# charlie_heart.net
KiCad netlist of a schematic drawn in EAGLE
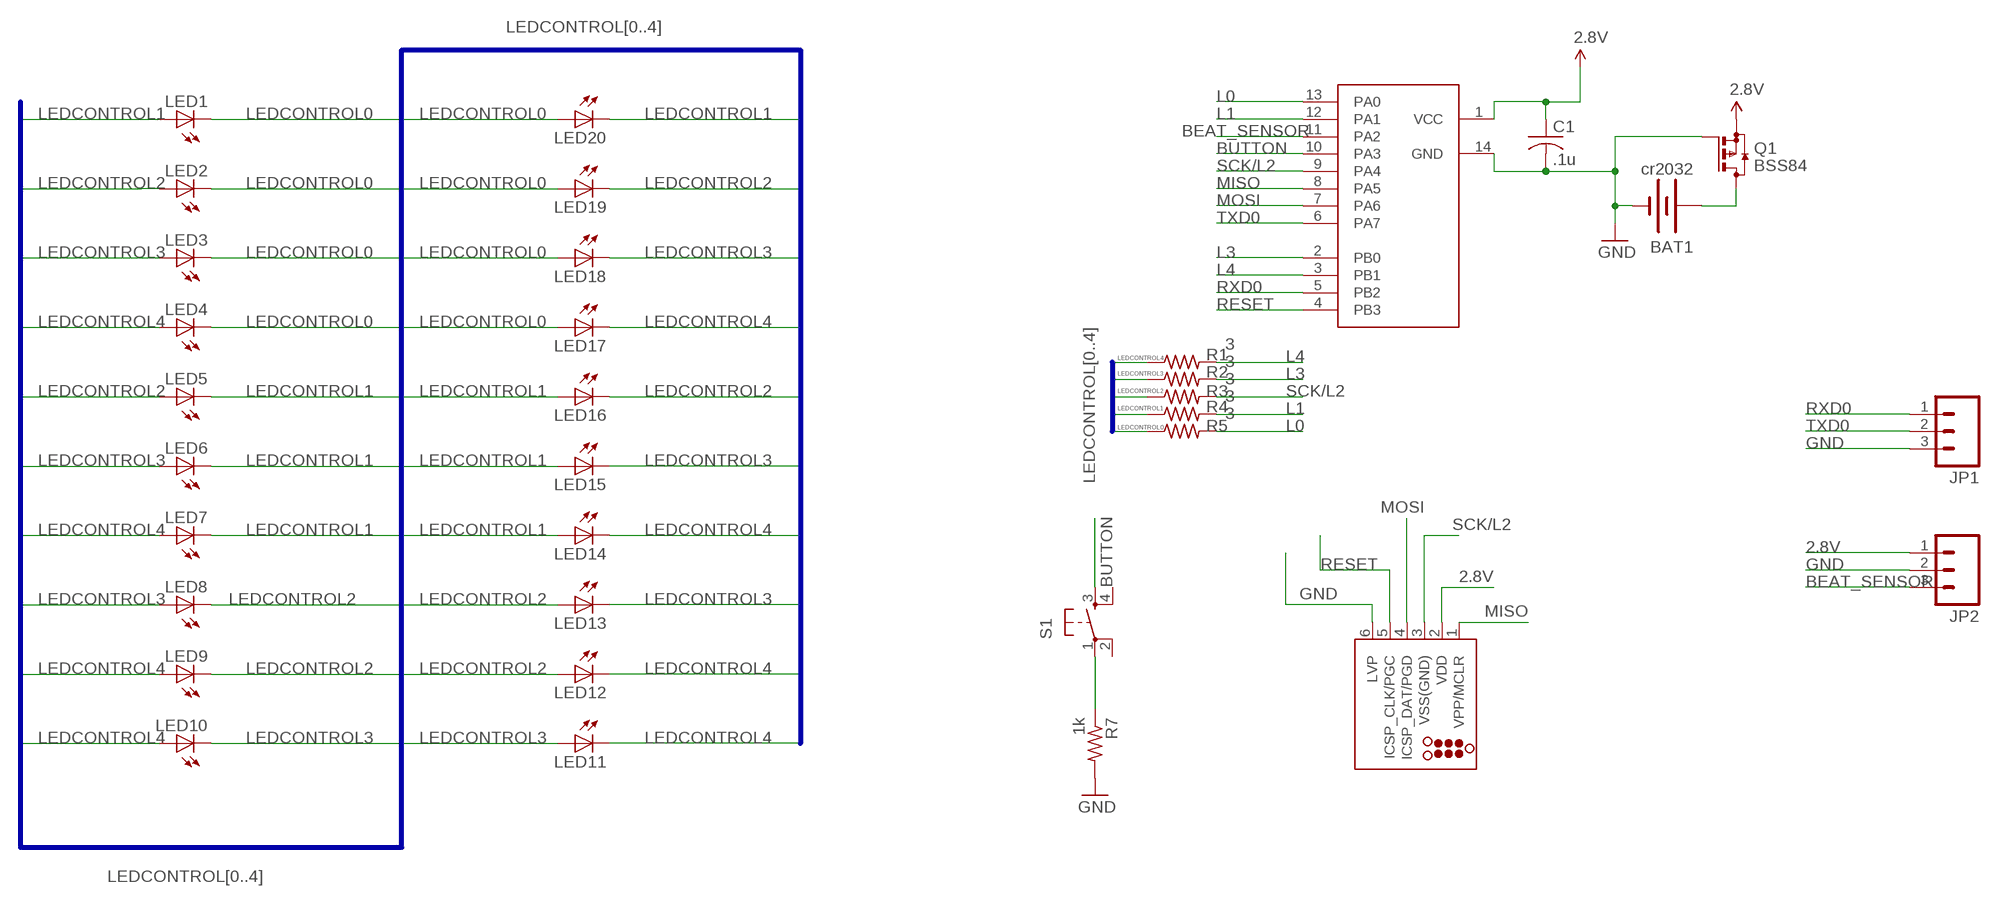
[diagram p0: schematic, sheet 1]

(export (version "E")
  (design (tool "Eeschema 10.0.6"))
  (components
    (comp (ref "BAT1")
      (value "cr2032")
      (footprint "eagle-import:BATTCON_20MM")
      (libsource (lib "eagle-import") (part "BATTERY20SMD"))
    )
    (comp (ref "C1")
      (value ".1u")
      (footprint "eagle-import:C1206")
      (libsource (lib "eagle-import") (part "C-USC1206"))
    )
    (comp (ref "J1")
      (value "TC2030-MCP-NL")
      (footprint "eagle-import:TC2030-MCP-NL")
      (libsource (lib "eagle-import") (part "TC2030-MCP-NL"))
    )
    (comp (ref "JP1")
      (value "M031X03_NO_SILK")
      (footprint "eagle-import:1X03_NO_SILK")
      (libsource (lib "eagle-import") (part "M031X03_NO_SILK"))
    )
    (comp (ref "JP2")
      (value "M031X03_NO_SILK")
      (footprint "eagle-import:1X03_NO_SILK")
      (libsource (lib "eagle-import") (part "M031X03_NO_SILK"))
    )
    (comp (ref "LED1")
      (value "LEDCHIP-LED0805")
      (footprint "eagle-import:CHIP-LED0805")
      (libsource (lib "eagle-import") (part "LEDCHIP-LED0805"))
    )
    (comp (ref "LED2")
      (value "LEDCHIP-LED0805")
      (footprint "eagle-import:CHIP-LED0805")
      (libsource (lib "eagle-import") (part "LEDCHIP-LED0805"))
    )
    (comp (ref "LED3")
      (value "LEDCHIP-LED0805")
      (footprint "eagle-import:CHIP-LED0805")
      (libsource (lib "eagle-import") (part "LEDCHIP-LED0805"))
    )
    (comp (ref "LED4")
      (value "LEDCHIP-LED0805")
      (footprint "eagle-import:CHIP-LED0805")
      (libsource (lib "eagle-import") (part "LEDCHIP-LED0805"))
    )
    (comp (ref "LED5")
      (value "LEDCHIP-LED0805")
      (footprint "eagle-import:CHIP-LED0805")
      (libsource (lib "eagle-import") (part "LEDCHIP-LED0805"))
    )
    (comp (ref "LED6")
      (value "LEDCHIP-LED0805")
      (footprint "eagle-import:CHIP-LED0805")
      (libsource (lib "eagle-import") (part "LEDCHIP-LED0805"))
    )
    (comp (ref "LED7")
      (value "LEDCHIP-LED0805")
      (footprint "eagle-import:CHIP-LED0805")
      (libsource (lib "eagle-import") (part "LEDCHIP-LED0805"))
    )
    (comp (ref "LED8")
      (value "LEDCHIP-LED0805")
      (footprint "eagle-import:CHIP-LED0805")
      (libsource (lib "eagle-import") (part "LEDCHIP-LED0805"))
    )
    (comp (ref "LED9")
      (value "LEDCHIP-LED0805")
      (footprint "eagle-import:CHIP-LED0805")
      (libsource (lib "eagle-import") (part "LEDCHIP-LED0805"))
    )
    (comp (ref "LED10")
      (value "LEDCHIP-LED0805")
      (footprint "eagle-import:CHIP-LED0805")
      (libsource (lib "eagle-import") (part "LEDCHIP-LED0805"))
    )
    (comp (ref "LED11")
      (value "LEDCHIP-LED0805")
      (footprint "eagle-import:CHIP-LED0805")
      (libsource (lib "eagle-import") (part "LEDCHIP-LED0805"))
    )
    (comp (ref "LED12")
      (value "LEDCHIP-LED0805")
      (footprint "eagle-import:CHIP-LED0805")
      (libsource (lib "eagle-import") (part "LEDCHIP-LED0805"))
    )
    (comp (ref "LED13")
      (value "LEDCHIP-LED0805")
      (footprint "eagle-import:CHIP-LED0805")
      (libsource (lib "eagle-import") (part "LEDCHIP-LED0805"))
    )
    (comp (ref "LED14")
      (value "LEDCHIP-LED0805")
      (footprint "eagle-import:CHIP-LED0805")
      (libsource (lib "eagle-import") (part "LEDCHIP-LED0805"))
    )
    (comp (ref "LED15")
      (value "LEDCHIP-LED0805")
      (footprint "eagle-import:CHIP-LED0805")
      (libsource (lib "eagle-import") (part "LEDCHIP-LED0805"))
    )
    (comp (ref "LED16")
      (value "LEDCHIP-LED0805")
      (footprint "eagle-import:CHIP-LED0805")
      (libsource (lib "eagle-import") (part "LEDCHIP-LED0805"))
    )
    (comp (ref "LED17")
      (value "LEDCHIP-LED0805")
      (footprint "eagle-import:CHIP-LED0805")
      (libsource (lib "eagle-import") (part "LEDCHIP-LED0805"))
    )
    (comp (ref "LED18")
      (value "LEDCHIP-LED0805")
      (footprint "eagle-import:CHIP-LED0805")
      (libsource (lib "eagle-import") (part "LEDCHIP-LED0805"))
    )
    (comp (ref "LED19")
      (value "LEDCHIP-LED0805")
      (footprint "eagle-import:CHIP-LED0805")
      (libsource (lib "eagle-import") (part "LEDCHIP-LED0805"))
    )
    (comp (ref "LED20")
      (value "LEDCHIP-LED0805")
      (footprint "eagle-import:CHIP-LED0805")
      (libsource (lib "eagle-import") (part "LEDCHIP-LED0805"))
    )
    (comp (ref "Q1")
      (value "BSS84")
      (footprint "eagle-import:SOT23")
      (libsource (lib "eagle-import") (part "BSS84"))
    )
    (comp (ref "R1")
      (value "3")
      (footprint "eagle-import:R0805")
      (libsource (lib "eagle-import") (part "R-US_R0805"))
    )
    (comp (ref "R2")
      (value "3")
      (footprint "eagle-import:R0805")
      (libsource (lib "eagle-import") (part "R-US_R0805"))
    )
    (comp (ref "R3")
      (value "3")
      (footprint "eagle-import:R0805")
      (libsource (lib "eagle-import") (part "R-US_R0805"))
    )
    (comp (ref "R4")
      (value "3")
      (footprint "eagle-import:R0805")
      (libsource (lib "eagle-import") (part "R-US_R0805"))
    )
    (comp (ref "R5")
      (value "3")
      (footprint "eagle-import:R0805")
      (libsource (lib "eagle-import") (part "R-US_R0805"))
    )
    (comp (ref "R7")
      (value "1k")
      (footprint "eagle-import:R0805")
      (libsource (lib "eagle-import") (part "R-US_R0805"))
    )
    (comp (ref "S1")
      (value "TAC_SWITCHSMD")
      (footprint "eagle-import:TACTILE_SWITCH_SMD")
      (libsource (lib "eagle-import") (part "TAC_SWITCHSMD"))
    )
    (comp (ref "U1")
      (value "ATTINY841")
      (footprint "eagle-import:SOIC127P600X175-14N")
      (libsource (lib "eagle-import") (part "ATTINY841-SSU"))
    )
  )
  (nets
    (net (code "1") (name "/BEAT_SENSOR") (class "Default")
      (node (ref "JP2") (pin "3") (pinfunction "3_3") (pintype "passive"))
      (node (ref "U1") (pin "11") (pinfunction "PA2_11") (pintype "bidirectional"))
    )
    (net (code "2") (name "/BUTTON") (class "Default")
      (node (ref "S1") (pin "3") (pinfunction "3_3") (pintype "passive"))
      (node (ref "U1") (pin "10") (pinfunction "PA3_10") (pintype "bidirectional"))
    )
    (net (code "3") (name "/L0") (class "Default")
      (node (ref "R5") (pin "2") (pinfunction "2_2") (pintype "passive"))
      (node (ref "U1") (pin "13") (pinfunction "PA0_13") (pintype "bidirectional"))
    )
    (net (code "4") (name "/L1") (class "Default")
      (node (ref "R4") (pin "2") (pinfunction "2_2") (pintype "passive"))
      (node (ref "U1") (pin "12") (pinfunction "PA1_12") (pintype "bidirectional"))
    )
    (net (code "5") (name "/L3") (class "Default")
      (node (ref "R2") (pin "2") (pinfunction "2_2") (pintype "passive"))
      (node (ref "U1") (pin "2") (pinfunction "PB0_2") (pintype "bidirectional"))
    )
    (net (code "6") (name "/L4") (class "Default")
      (node (ref "R1") (pin "2") (pinfunction "2_2") (pintype "passive"))
      (node (ref "U1") (pin "3") (pinfunction "PB1_3") (pintype "bidirectional"))
    )
    (net (code "7") (name "/LEDCONTROL0") (class "Default")
      (node (ref "LED1") (pin "C") (pinfunction "C_C") (pintype "passive"))
      (node (ref "LED17") (pin "A") (pinfunction "A_A") (pintype "passive"))
      (node (ref "LED18") (pin "A") (pinfunction "A_A") (pintype "passive"))
      (node (ref "LED19") (pin "A") (pinfunction "A_A") (pintype "passive"))
      (node (ref "LED2") (pin "C") (pinfunction "C_C") (pintype "passive"))
      (node (ref "LED20") (pin "A") (pinfunction "A_A") (pintype "passive"))
      (node (ref "LED3") (pin "C") (pinfunction "C_C") (pintype "passive"))
      (node (ref "LED4") (pin "C") (pinfunction "C_C") (pintype "passive"))
      (node (ref "R5") (pin "1") (pinfunction "1_1") (pintype "passive"))
    )
    (net (code "8") (name "/LEDCONTROL1") (class "Default")
      (node (ref "LED1") (pin "A") (pinfunction "A_A") (pintype "passive"))
      (node (ref "LED14") (pin "A") (pinfunction "A_A") (pintype "passive"))
      (node (ref "LED15") (pin "A") (pinfunction "A_A") (pintype "passive"))
      (node (ref "LED16") (pin "A") (pinfunction "A_A") (pintype "passive"))
      (node (ref "LED20") (pin "C") (pinfunction "C_C") (pintype "passive"))
      (node (ref "LED5") (pin "C") (pinfunction "C_C") (pintype "passive"))
      (node (ref "LED6") (pin "C") (pinfunction "C_C") (pintype "passive"))
      (node (ref "LED7") (pin "C") (pinfunction "C_C") (pintype "passive"))
      (node (ref "R4") (pin "1") (pinfunction "1_1") (pintype "passive"))
    )
    (net (code "9") (name "/LEDCONTROL2") (class "Default")
      (node (ref "LED12") (pin "A") (pinfunction "A_A") (pintype "passive"))
      (node (ref "LED13") (pin "A") (pinfunction "A_A") (pintype "passive"))
      (node (ref "LED16") (pin "C") (pinfunction "C_C") (pintype "passive"))
      (node (ref "LED19") (pin "C") (pinfunction "C_C") (pintype "passive"))
      (node (ref "LED2") (pin "A") (pinfunction "A_A") (pintype "passive"))
      (node (ref "LED5") (pin "A") (pinfunction "A_A") (pintype "passive"))
      (node (ref "LED8") (pin "C") (pinfunction "C_C") (pintype "passive"))
      (node (ref "LED9") (pin "C") (pinfunction "C_C") (pintype "passive"))
      (node (ref "R3") (pin "1") (pinfunction "1_1") (pintype "passive"))
    )
    (net (code "10") (name "/LEDCONTROL3") (class "Default")
      (node (ref "LED10") (pin "C") (pinfunction "C_C") (pintype "passive"))
      (node (ref "LED11") (pin "A") (pinfunction "A_A") (pintype "passive"))
      (node (ref "LED13") (pin "C") (pinfunction "C_C") (pintype "passive"))
      (node (ref "LED15") (pin "C") (pinfunction "C_C") (pintype "passive"))
      (node (ref "LED18") (pin "C") (pinfunction "C_C") (pintype "passive"))
      (node (ref "LED3") (pin "A") (pinfunction "A_A") (pintype "passive"))
      (node (ref "LED6") (pin "A") (pinfunction "A_A") (pintype "passive"))
      (node (ref "LED8") (pin "A") (pinfunction "A_A") (pintype "passive"))
      (node (ref "R2") (pin "1") (pinfunction "1_1") (pintype "passive"))
    )
    (net (code "11") (name "/LEDCONTROL4") (class "Default")
      (node (ref "LED10") (pin "A") (pinfunction "A_A") (pintype "passive"))
      (node (ref "LED11") (pin "C") (pinfunction "C_C") (pintype "passive"))
      (node (ref "LED12") (pin "C") (pinfunction "C_C") (pintype "passive"))
      (node (ref "LED14") (pin "C") (pinfunction "C_C") (pintype "passive"))
      (node (ref "LED17") (pin "C") (pinfunction "C_C") (pintype "passive"))
      (node (ref "LED4") (pin "A") (pinfunction "A_A") (pintype "passive"))
      (node (ref "LED7") (pin "A") (pinfunction "A_A") (pintype "passive"))
      (node (ref "LED9") (pin "A") (pinfunction "A_A") (pintype "passive"))
      (node (ref "R1") (pin "1") (pinfunction "1_1") (pintype "passive"))
    )
    (net (code "13") (name "/MISO") (class "Default")
      (node (ref "J1") (pin "1") (pinfunction "VPP/MCLR_1") (pintype "passive"))
      (node (ref "U1") (pin "8") (pinfunction "PA5_8") (pintype "bidirectional"))
    )
    (net (code "14") (name "/MOSI") (class "Default")
      (node (ref "J1") (pin "4") (pinfunction "ICSP_DAT/PGD_4") (pintype "bidirectional"))
      (node (ref "U1") (pin "7") (pinfunction "PA6_7") (pintype "bidirectional"))
    )
    (net (code "15") (name "/RESET") (class "Default")
      (node (ref "J1") (pin "5") (pinfunction "ICSP_CLK/PGC_5") (pintype "output"))
      (node (ref "U1") (pin "4") (pinfunction "PB3_4") (pintype "bidirectional"))
    )
    (net (code "16") (name "/RXD0") (class "Default")
      (node (ref "JP1") (pin "1") (pinfunction "1_1") (pintype "passive"))
      (node (ref "U1") (pin "5") (pinfunction "PB2_5") (pintype "bidirectional"))
    )
    (net (code "17") (name "/SCK{slash}L2") (class "Default")
      (node (ref "J1") (pin "3") (pinfunction "VSS(GND)_3") (pintype "power_in"))
      (node (ref "R3") (pin "2") (pinfunction "2_2") (pintype "passive"))
      (node (ref "U1") (pin "9") (pinfunction "PA4_9") (pintype "bidirectional"))
    )
    (net (code "18") (name "/TXD0") (class "Default")
      (node (ref "JP1") (pin "2") (pinfunction "2_2") (pintype "passive"))
      (node (ref "U1") (pin "6") (pinfunction "PA7_6") (pintype "bidirectional"))
    )
    (net (code "19") (name "2.8V") (class "Default")
      (node (ref "C1") (pin "1") (pinfunction "1_1") (pintype "passive"))
      (node (ref "J1") (pin "2") (pinfunction "VDD_2") (pintype "power_in"))
      (node (ref "JP2") (pin "1") (pinfunction "1_1") (pintype "passive"))
      (node (ref "Q1") (pin "2") (pinfunction "S_2") (pintype "passive"))
      (node (ref "U1") (pin "1") (pinfunction "VCC_1") (pintype "power_in"))
    )
    (net (code "20") (name "GND") (class "Default")
      (node (ref "BAT1") (pin "2") (pinfunction "-_2") (pintype "power_in"))
      (node (ref "C1") (pin "2") (pinfunction "2_2") (pintype "passive"))
      (node (ref "J1") (pin "6") (pinfunction "LVP_6") (pintype "bidirectional"))
      (node (ref "JP1") (pin "3") (pinfunction "3_3") (pintype "passive"))
      (node (ref "JP2") (pin "2") (pinfunction "2_2") (pintype "passive"))
      (node (ref "Q1") (pin "1") (pinfunction "G_1") (pintype "passive"))
      (node (ref "R7") (pin "2") (pinfunction "2_2") (pintype "passive"))
      (node (ref "U1") (pin "14") (pinfunction "GND_14") (pintype "power_in"))
    )
    (net (code "21") (name "Net-(BAT1-+)") (class "Default")
      (node (ref "BAT1") (pin "1") (pinfunction "+_1") (pintype "power_in"))
      (node (ref "Q1") (pin "3") (pinfunction "D_3") (pintype "passive"))
    )
    (net (code "22") (name "Net-(R7-Pad1)") (class "Default")
      (node (ref "R7") (pin "1") (pinfunction "1_1") (pintype "passive"))
      (node (ref "S1") (pin "1") (pinfunction "1_1") (pintype "passive"))
    )
    (net (code "23") (name "unconnected-(S1-Pad2)") (class "Default")
      (node (ref "S1") (pin "2") (pinfunction "2_2") (pintype "passive"))
    )
    (net (code "24") (name "unconnected-(S1-Pad4)") (class "Default")
      (node (ref "S1") (pin "4") (pinfunction "4_4") (pintype "passive"))
    )
  )
)
